# LB_BIT_i31_OSCILLATOR-v03_5_7_-OHW.net
KiCad netlist of a schematic drawn in EAGLE
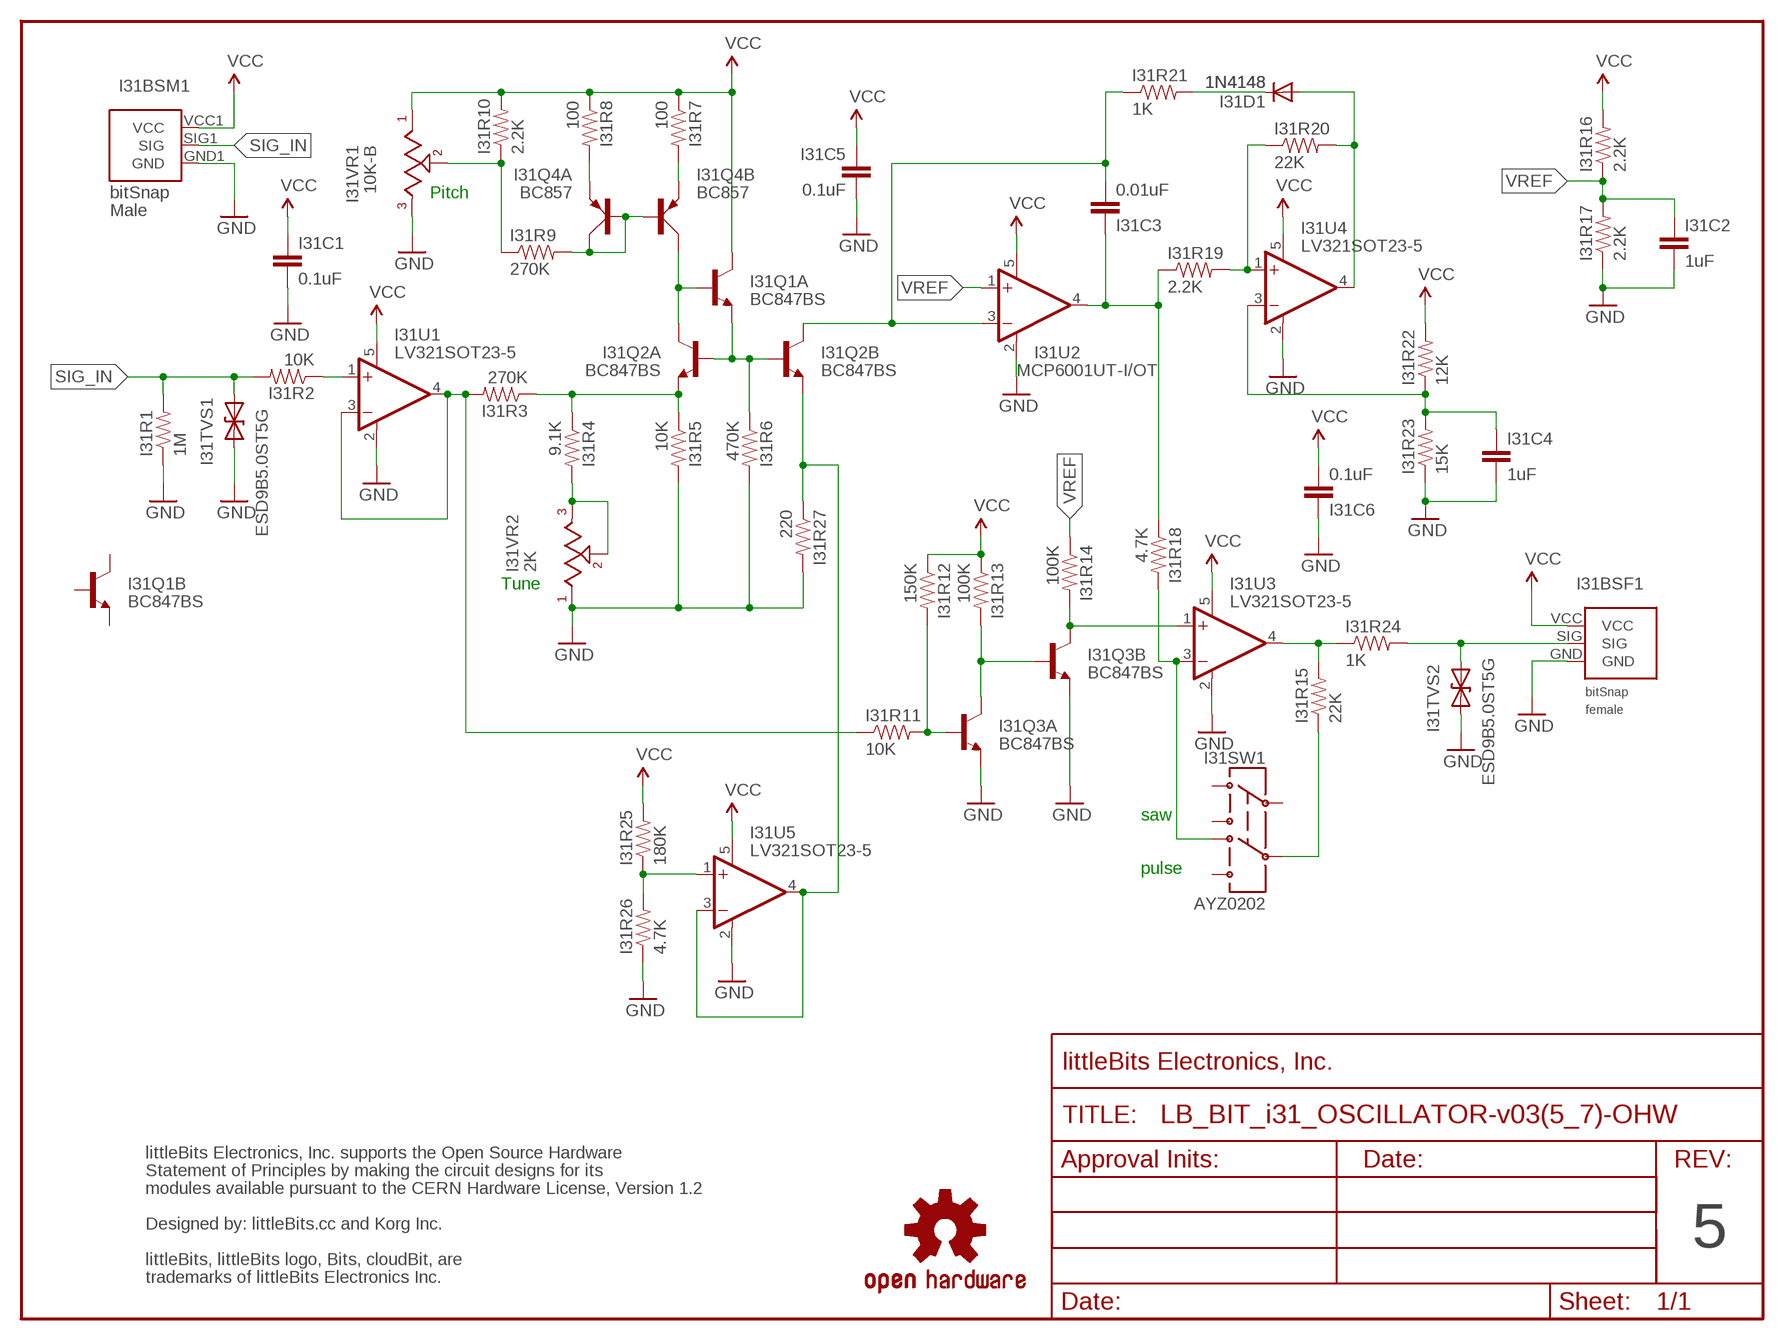
[diagram p0: schematic, sheet 1]

(export (version "E")
  (design (tool "Eeschema 10.0.6"))
  (components
    (comp (ref "I31BSF1")
      (value "BITSNAP_V03_FEMALE")
      (footprint "eagle-import:BITSNAP_V03_FEMALE")
      (libsource (lib "eagle-import") (part "BITSNAP_V03_FEMALE"))
    )
    (comp (ref "I31BSM1")
      (value "BITSNAP_V03_MALE")
      (footprint "eagle-import:BITSNAP_V03_MALE")
      (libsource (lib "eagle-import") (part "BITSNAP_V03_MALE"))
    )
    (comp (ref "I31C1")
      (value "0.1uF")
      (footprint "eagle-import:CAP-0603")
      (libsource (lib "eagle-import") (part "CAPCAP-0603"))
    )
    (comp (ref "I31C2")
      (value "1uF")
      (footprint "eagle-import:CAP-0603")
      (libsource (lib "eagle-import") (part "CAPCAP-0603"))
    )
    (comp (ref "I31C3")
      (value "0.01uF")
      (footprint "eagle-import:CAP-0603")
      (libsource (lib "eagle-import") (part "CAPCAP-0603"))
    )
    (comp (ref "I31C4")
      (value "1uF")
      (footprint "eagle-import:CAP-0603")
      (libsource (lib "eagle-import") (part "CAPCAP-0603"))
    )
    (comp (ref "I31C5")
      (value "0.1uF")
      (footprint "eagle-import:CAP-0603")
      (libsource (lib "eagle-import") (part "CAPCAP-0603"))
    )
    (comp (ref "I31C6")
      (value "0.1uF")
      (footprint "eagle-import:CAP-0603")
      (libsource (lib "eagle-import") (part "CAPCAP-0603"))
    )
    (comp (ref "I31D1")
      (value "1N4148")
      (footprint "eagle-import:SOD-323")
      (libsource (lib "eagle-import") (part "DIODESOD"))
    )
    (comp (ref "I31Q1")
      (value "BC847BS")
      (footprint "eagle-import:SOT-363_PHILLIPS")
      (libsource (lib "eagle-import") (part "TRANS-BJT_NPN-DUAL-BC847BS"))
    )
    (comp (ref "I31Q2")
      (value "BC847BS")
      (footprint "eagle-import:SOT-363_PHILLIPS")
      (libsource (lib "eagle-import") (part "TRANS-BJT_NPN-DUAL-BC847BS"))
    )
    (comp (ref "I31Q3")
      (value "BC847BS")
      (footprint "eagle-import:SOT-363_PHILLIPS")
      (libsource (lib "eagle-import") (part "TRANS-BJT_NPN-DUAL-BC847BS"))
    )
    (comp (ref "I31Q4")
      (value "BC857")
      (footprint "eagle-import:SOT-363_PHILLIPS")
      (libsource (lib "eagle-import") (part "TRANS-BJT_PNP-DUALBC857"))
    )
    (comp (ref "I31R1")
      (value "1M")
      (footprint "eagle-import:RES-0603")
      (libsource (lib "eagle-import") (part "RESISTOR0603"))
    )
    (comp (ref "I31R2")
      (value "10K")
      (footprint "eagle-import:RES-0603")
      (libsource (lib "eagle-import") (part "RESISTOR0603"))
    )
    (comp (ref "I31R3")
      (value "270K")
      (footprint "eagle-import:RES-0603")
      (libsource (lib "eagle-import") (part "RESISTOR0603"))
    )
    (comp (ref "I31R4")
      (value "9.1K")
      (footprint "eagle-import:RES-0603")
      (libsource (lib "eagle-import") (part "RESISTOR0603"))
    )
    (comp (ref "I31R5")
      (value "10K")
      (footprint "eagle-import:RES-0603")
      (libsource (lib "eagle-import") (part "RESISTOR0603"))
    )
    (comp (ref "I31R6")
      (value "470K")
      (footprint "eagle-import:RES-0603")
      (libsource (lib "eagle-import") (part "RESISTOR0603"))
    )
    (comp (ref "I31R7")
      (value "100")
      (footprint "eagle-import:RES-0603")
      (libsource (lib "eagle-import") (part "RESISTOR0603"))
    )
    (comp (ref "I31R8")
      (value "100")
      (footprint "eagle-import:RES-0603")
      (libsource (lib "eagle-import") (part "RESISTOR0603"))
    )
    (comp (ref "I31R9")
      (value "270K")
      (footprint "eagle-import:RES-0603")
      (libsource (lib "eagle-import") (part "RESISTOR0603"))
    )
    (comp (ref "I31R10")
      (value "2.2K")
      (footprint "eagle-import:RES-0603")
      (libsource (lib "eagle-import") (part "RESISTOR0603"))
    )
    (comp (ref "I31R11")
      (value "10K")
      (footprint "eagle-import:RES-0603")
      (libsource (lib "eagle-import") (part "RESISTOR0603"))
    )
    (comp (ref "I31R12")
      (value "150K")
      (footprint "eagle-import:RES-0603")
      (libsource (lib "eagle-import") (part "RESISTOR0603"))
    )
    (comp (ref "I31R13")
      (value "100K")
      (footprint "eagle-import:RES-0603")
      (libsource (lib "eagle-import") (part "RESISTOR0603"))
    )
    (comp (ref "I31R14")
      (value "100K")
      (footprint "eagle-import:RES-0603")
      (libsource (lib "eagle-import") (part "RESISTOR0603"))
    )
    (comp (ref "I31R15")
      (value "22K")
      (footprint "eagle-import:RES-0603")
      (libsource (lib "eagle-import") (part "RESISTOR0603"))
    )
    (comp (ref "I31R16")
      (value "2.2K")
      (footprint "eagle-import:RES-0603")
      (libsource (lib "eagle-import") (part "RESISTOR0603"))
    )
    (comp (ref "I31R17")
      (value "2.2K")
      (footprint "eagle-import:RES-0603")
      (libsource (lib "eagle-import") (part "RESISTOR0603"))
    )
    (comp (ref "I31R18")
      (value "4.7K")
      (footprint "eagle-import:RES-0603")
      (libsource (lib "eagle-import") (part "RESISTOR0603"))
    )
    (comp (ref "I31R19")
      (value "2.2K")
      (footprint "eagle-import:RES-0603")
      (libsource (lib "eagle-import") (part "RESISTOR0603"))
    )
    (comp (ref "I31R20")
      (value "22K")
      (footprint "eagle-import:RES-0603")
      (libsource (lib "eagle-import") (part "RESISTOR0603"))
    )
    (comp (ref "I31R21")
      (value "1K")
      (footprint "eagle-import:RES-0603")
      (libsource (lib "eagle-import") (part "RESISTOR0603"))
    )
    (comp (ref "I31R22")
      (value "12K")
      (footprint "eagle-import:RES-0603")
      (libsource (lib "eagle-import") (part "RESISTOR0603"))
    )
    (comp (ref "I31R23")
      (value "15K")
      (footprint "eagle-import:RES-0603")
      (libsource (lib "eagle-import") (part "RESISTOR0603"))
    )
    (comp (ref "I31R24")
      (value "1K")
      (footprint "eagle-import:RES-0603")
      (libsource (lib "eagle-import") (part "RESISTOR0603"))
    )
    (comp (ref "I31R25")
      (value "180K")
      (footprint "eagle-import:RES-0603")
      (libsource (lib "eagle-import") (part "RESISTOR0603"))
    )
    (comp (ref "I31R26")
      (value "4.7K")
      (footprint "eagle-import:RES-0603")
      (libsource (lib "eagle-import") (part "RESISTOR0603"))
    )
    (comp (ref "I31R27")
      (value "220")
      (footprint "eagle-import:RES-0603")
      (libsource (lib "eagle-import") (part "RESISTOR0603"))
    )
    (comp (ref "I31SW1")
      (value "AYZ0202")
      (footprint "eagle-import:AYZ0202")
      (libsource (lib "eagle-import") (part "AYZ0202"))
    )
    (comp (ref "I31TVS1")
      (value "ESD9B5.0ST5G")
      (footprint "eagle-import:SOD-923")
      (libsource (lib "eagle-import") (part "DIODE-TVSSOD-923"))
    )
    (comp (ref "I31TVS2")
      (value "ESD9B5.0ST5G")
      (footprint "eagle-import:SOD-923")
      (libsource (lib "eagle-import") (part "DIODE-TVSSOD-923"))
    )
    (comp (ref "I31U1")
      (value "LV321SOT23-5")
      (footprint "eagle-import:SOT23-5")
      (libsource (lib "eagle-import") (part "LV321SOT23-5"))
    )
    (comp (ref "I31U2")
      (value "MCP6001UT")
      (footprint "eagle-import:SOT23-5")
      (libsource (lib "eagle-import") (part "LV321SOT23-5"))
    )
    (comp (ref "I31U3")
      (value "LV321SOT23-5")
      (footprint "eagle-import:SOT23-5")
      (libsource (lib "eagle-import") (part "LV321SOT23-5"))
    )
    (comp (ref "I31U4")
      (value "LV321SOT23-5")
      (footprint "eagle-import:SOT23-5")
      (libsource (lib "eagle-import") (part "LV321SOT23-5"))
    )
    (comp (ref "I31U5")
      (value "LV321SOT23-5")
      (footprint "eagle-import:SOT23-5")
      (libsource (lib "eagle-import") (part "LV321SOT23-5"))
    )
    (comp (ref "I31VR1")
      (value "10K-B")
      (footprint "eagle-import:ALPS_POT")
      (libsource (lib "eagle-import") (part "ALPS_POTTH"))
    )
    (comp (ref "I31VR2")
      (value "2K")
      (footprint "eagle-import:THUMBPOT-BOURNS_3352")
      (libsource (lib "eagle-import") (part "THUMBPOT-BOURNS_3352P"))
    )
    (comp (ref "U$2")
      (value "FRAME-LETTER-OHWOHW")
      (footprint "eagle-import:FABDWG01-OHW")
      (libsource (lib "eagle-import") (part "FRAME-LETTER-OHWOHW"))
    )
    (comp (ref "U$3")
      (value "OSHW-LOGOL")
      (footprint "eagle-import:OSHW-LOGO-L")
      (libsource (lib "eagle-import") (part "OSHW-LOGOL"))
    )
    (comp (ref "U$4")
      (value "OSHWCREDIT-KORG")
      (footprint "eagle-import:OSHWCREDIT-KORG")
      (libsource (lib "eagle-import") (part "OSHWCREDIT-KORG"))
    )
  )
  (nets
    (net (code "1") (name "GND") (class "Default")
      (node (ref "I31BSF1") (pin "GND") (pinfunction "GND_GND") (pintype "bidirectional"))
      (node (ref "I31BSM1") (pin "GND1") (pinfunction "GND_GND1") (pintype "bidirectional"))
      (node (ref "I31C1") (pin "2") (pinfunction "2_2") (pintype "passive"))
      (node (ref "I31C2") (pin "2") (pinfunction "2_2") (pintype "passive"))
      (node (ref "I31C4") (pin "2") (pinfunction "2_2") (pintype "passive"))
      (node (ref "I31C5") (pin "2") (pinfunction "2_2") (pintype "passive"))
      (node (ref "I31C6") (pin "1") (pinfunction "1_1") (pintype "passive"))
      (node (ref "I31Q3") (pin "1") (pinfunction "E_1") (pintype "passive"))
      (node (ref "I31Q3") (pin "4") (pinfunction "E_4") (pintype "passive"))
      (node (ref "I31R1") (pin "1") (pinfunction "1_1") (pintype "passive"))
      (node (ref "I31R17") (pin "1") (pinfunction "1_1") (pintype "passive"))
      (node (ref "I31R23") (pin "1") (pinfunction "1_1") (pintype "passive"))
      (node (ref "I31R26") (pin "1") (pinfunction "1_1") (pintype "passive"))
      (node (ref "I31R27") (pin "2") (pinfunction "2_2") (pintype "passive"))
      (node (ref "I31R5") (pin "2") (pinfunction "2_2") (pintype "passive"))
      (node (ref "I31R6") (pin "2") (pinfunction "2_2") (pintype "passive"))
      (node (ref "I31TVS1") (pin "1") (pinfunction "A_1") (pintype "passive"))
      (node (ref "I31TVS2") (pin "1") (pinfunction "A_1") (pintype "passive"))
      (node (ref "I31U1") (pin "2") (pinfunction "V-_2") (pintype "power_in"))
      (node (ref "I31U2") (pin "2") (pinfunction "V-_2") (pintype "power_in"))
      (node (ref "I31U3") (pin "2") (pinfunction "V-_2") (pintype "power_in"))
      (node (ref "I31U4") (pin "2") (pinfunction "V-_2") (pintype "power_in"))
      (node (ref "I31U5") (pin "2") (pinfunction "V-_2") (pintype "power_in"))
      (node (ref "I31VR1") (pin "3") (pinfunction "3_3") (pintype "passive"))
      (node (ref "I31VR2") (pin "3") (pinfunction "1_3") (pintype "passive"))
    )
    (net (code "2") (name "Net-(I31D1-A)") (class "Default")
      (node (ref "I31D1") (pin "2") (pinfunction "A_2") (pintype "passive"))
      (node (ref "I31R20") (pin "2") (pinfunction "2_2") (pintype "passive"))
      (node (ref "I31U4") (pin "4") (pinfunction "OUT_4") (pintype "output"))
    )
    (net (code "3") (name "Net-(I31D1-C)") (class "Default")
      (node (ref "I31D1") (pin "1") (pinfunction "C_1") (pintype "passive"))
      (node (ref "I31R21") (pin "2") (pinfunction "2_2") (pintype "passive"))
    )
    (net (code "4") (name "Net-(I31Q1A-B)") (class "Default")
      (node (ref "I31Q1") (pin "2") (pinfunction "B_2") (pintype "passive"))
      (node (ref "I31Q2") (pin "6") (pinfunction "C_6") (pintype "passive"))
      (node (ref "I31Q4") (pin "3") (pinfunction "C_3") (pintype "passive"))
    )
    (net (code "5") (name "Net-(I31Q1A-E)") (class "Default")
      (node (ref "I31Q1") (pin "1") (pinfunction "E_1") (pintype "passive"))
      (node (ref "I31Q2") (pin "2") (pinfunction "B_2") (pintype "passive"))
      (node (ref "I31Q2") (pin "5") (pinfunction "B_5") (pintype "passive"))
      (node (ref "I31R6") (pin "1") (pinfunction "1_1") (pintype "passive"))
    )
    (net (code "6") (name "Net-(I31Q2A-E)") (class "Default")
      (node (ref "I31Q2") (pin "1") (pinfunction "E_1") (pintype "passive"))
      (node (ref "I31R3") (pin "1") (pinfunction "1_1") (pintype "passive"))
      (node (ref "I31R4") (pin "1") (pinfunction "1_1") (pintype "passive"))
      (node (ref "I31R5") (pin "1") (pinfunction "1_1") (pintype "passive"))
    )
    (net (code "7") (name "Net-(I31Q2B-C)") (class "Default")
      (node (ref "I31C3") (pin "2") (pinfunction "2_2") (pintype "passive"))
      (node (ref "I31Q2") (pin "3") (pinfunction "C_3") (pintype "passive"))
      (node (ref "I31R21") (pin "1") (pinfunction "1_1") (pintype "passive"))
      (node (ref "I31U2") (pin "3") (pinfunction "-IN_3") (pintype "input"))
    )
    (net (code "8") (name "Net-(I31Q2B-E)") (class "Default")
      (node (ref "I31Q2") (pin "4") (pinfunction "E_4") (pintype "passive"))
      (node (ref "I31R27") (pin "1") (pinfunction "1_1") (pintype "passive"))
      (node (ref "I31U5") (pin "3") (pinfunction "-IN_3") (pintype "input"))
      (node (ref "I31U5") (pin "4") (pinfunction "OUT_4") (pintype "output"))
    )
    (net (code "9") (name "Net-(I31Q3A-B)") (class "Default")
      (node (ref "I31Q3") (pin "2") (pinfunction "B_2") (pintype "passive"))
      (node (ref "I31R11") (pin "2") (pinfunction "2_2") (pintype "passive"))
      (node (ref "I31R12") (pin "2") (pinfunction "2_2") (pintype "passive"))
    )
    (net (code "10") (name "Net-(I31Q3A-C)") (class "Default")
      (node (ref "I31Q3") (pin "5") (pinfunction "B_5") (pintype "passive"))
      (node (ref "I31Q3") (pin "6") (pinfunction "C_6") (pintype "passive"))
      (node (ref "I31R13") (pin "2") (pinfunction "2_2") (pintype "passive"))
    )
    (net (code "11") (name "Net-(I31Q3B-C)") (class "Default")
      (node (ref "I31Q3") (pin "3") (pinfunction "C_3") (pintype "passive"))
      (node (ref "I31R14") (pin "2") (pinfunction "2_2") (pintype "passive"))
      (node (ref "I31U3") (pin "1") (pinfunction "+IN_1") (pintype "input"))
    )
    (net (code "12") (name "Net-(I31Q4A-B)") (class "Default")
      (node (ref "I31Q4") (pin "2") (pinfunction "B_2") (pintype "passive"))
      (node (ref "I31Q4") (pin "5") (pinfunction "B_5") (pintype "passive"))
      (node (ref "I31Q4") (pin "6") (pinfunction "C_6") (pintype "passive"))
      (node (ref "I31R9") (pin "2") (pinfunction "2_2") (pintype "passive"))
    )
    (net (code "13") (name "Net-(I31Q4A-E)") (class "Default")
      (node (ref "I31Q4") (pin "1") (pinfunction "E_1") (pintype "passive"))
      (node (ref "I31R8") (pin "2") (pinfunction "2_2") (pintype "passive"))
    )
    (net (code "14") (name "Net-(I31Q4B-E)") (class "Default")
      (node (ref "I31Q4") (pin "4") (pinfunction "E_4") (pintype "passive"))
      (node (ref "I31R7") (pin "2") (pinfunction "2_2") (pintype "passive"))
    )
    (net (code "15") (name "Net-(I31R10-Pad1)") (class "Default")
      (node (ref "I31R10") (pin "1") (pinfunction "1_1") (pintype "passive"))
      (node (ref "I31R9") (pin "1") (pinfunction "1_1") (pintype "passive"))
      (node (ref "I31VR1") (pin "2") (pinfunction "2_2") (pintype "passive"))
    )
    (net (code "16") (name "Net-(I31R15-Pad1)") (class "Default")
      (node (ref "I31R15") (pin "1") (pinfunction "1_1") (pintype "passive"))
      (node (ref "I31SW1") (pin "5") (pinfunction "5_5") (pintype "bidirectional"))
    )
    (net (code "17") (name "Net-(I31TVS2-C)") (class "Default")
      (node (ref "I31BSF1") (pin "SIG") (pinfunction "SIG_SIG") (pintype "bidirectional"))
      (node (ref "I31R24") (pin "2") (pinfunction "2_2") (pintype "passive"))
      (node (ref "I31TVS2") (pin "2") (pinfunction "C_2") (pintype "passive"))
    )
    (net (code "18") (name "Net-(I31U1-+IN)") (class "Default")
      (node (ref "I31R2") (pin "1") (pinfunction "1_1") (pintype "passive"))
      (node (ref "I31U1") (pin "1") (pinfunction "+IN_1") (pintype "input"))
    )
    (net (code "19") (name "Net-(I31U1--IN)") (class "Default")
      (node (ref "I31R11") (pin "1") (pinfunction "1_1") (pintype "passive"))
      (node (ref "I31R3") (pin "2") (pinfunction "2_2") (pintype "passive"))
      (node (ref "I31U1") (pin "3") (pinfunction "-IN_3") (pintype "input"))
      (node (ref "I31U1") (pin "4") (pinfunction "OUT_4") (pintype "output"))
    )
    (net (code "20") (name "Net-(I31U2-OUT)") (class "Default")
      (node (ref "I31C3") (pin "1") (pinfunction "1_1") (pintype "passive"))
      (node (ref "I31R18") (pin "1") (pinfunction "1_1") (pintype "passive"))
      (node (ref "I31R19") (pin "1") (pinfunction "1_1") (pintype "passive"))
      (node (ref "I31U2") (pin "4") (pinfunction "OUT_4") (pintype "output"))
    )
    (net (code "21") (name "Net-(I31U3--IN)") (class "Default")
      (node (ref "I31R18") (pin "2") (pinfunction "2_2") (pintype "passive"))
      (node (ref "I31SW1") (pin "4") (pinfunction "4_4") (pintype "bidirectional"))
      (node (ref "I31U3") (pin "3") (pinfunction "-IN_3") (pintype "input"))
    )
    (net (code "22") (name "Net-(I31U3-OUT)") (class "Default")
      (node (ref "I31R15") (pin "2") (pinfunction "2_2") (pintype "passive"))
      (node (ref "I31R24") (pin "1") (pinfunction "1_1") (pintype "passive"))
      (node (ref "I31U3") (pin "4") (pinfunction "OUT_4") (pintype "output"))
    )
    (net (code "23") (name "Net-(I31U4-+IN)") (class "Default")
      (node (ref "I31R19") (pin "2") (pinfunction "2_2") (pintype "passive"))
      (node (ref "I31R20") (pin "1") (pinfunction "1_1") (pintype "passive"))
      (node (ref "I31U4") (pin "1") (pinfunction "+IN_1") (pintype "input"))
    )
    (net (code "24") (name "Net-(I31U4--IN)") (class "Default")
      (node (ref "I31C4") (pin "1") (pinfunction "1_1") (pintype "passive"))
      (node (ref "I31R22") (pin "1") (pinfunction "1_1") (pintype "passive"))
      (node (ref "I31R23") (pin "2") (pinfunction "2_2") (pintype "passive"))
      (node (ref "I31U4") (pin "3") (pinfunction "-IN_3") (pintype "input"))
    )
    (net (code "25") (name "Net-(I31U5-+IN)") (class "Default")
      (node (ref "I31R25") (pin "1") (pinfunction "1_1") (pintype "passive"))
      (node (ref "I31R26") (pin "2") (pinfunction "2_2") (pintype "passive"))
      (node (ref "I31U5") (pin "1") (pinfunction "+IN_1") (pintype "input"))
    )
    (net (code "26") (name "Net-(I31VR2-3)") (class "Default")
      (node (ref "I31R4") (pin "2") (pinfunction "2_2") (pintype "passive"))
      (node (ref "I31VR2") (pin "1") (pinfunction "3_1") (pintype "passive"))
      (node (ref "I31VR2") (pin "2") (pinfunction "2_2") (pintype "passive"))
    )
    (net (code "27") (name "SIG_IN") (class "Default")
      (node (ref "I31BSM1") (pin "SIG1") (pinfunction "SIG_SIG1") (pintype "bidirectional"))
      (node (ref "I31R1") (pin "2") (pinfunction "2_2") (pintype "passive"))
      (node (ref "I31R2") (pin "2") (pinfunction "2_2") (pintype "passive"))
      (node (ref "I31TVS1") (pin "2") (pinfunction "C_2") (pintype "passive"))
    )
    (net (code "28") (name "VCC") (class "Default")
      (node (ref "I31BSF1") (pin "VCC") (pinfunction "VCC_VCC") (pintype "bidirectional"))
      (node (ref "I31BSM1") (pin "VCC1") (pinfunction "VCC_VCC1") (pintype "bidirectional"))
      (node (ref "I31C1") (pin "1") (pinfunction "1_1") (pintype "passive"))
      (node (ref "I31C5") (pin "1") (pinfunction "1_1") (pintype "passive"))
      (node (ref "I31C6") (pin "2") (pinfunction "2_2") (pintype "passive"))
      (node (ref "I31Q1") (pin "6") (pinfunction "C_6") (pintype "passive"))
      (node (ref "I31R10") (pin "2") (pinfunction "2_2") (pintype "passive"))
      (node (ref "I31R12") (pin "1") (pinfunction "1_1") (pintype "passive"))
      (node (ref "I31R13") (pin "1") (pinfunction "1_1") (pintype "passive"))
      (node (ref "I31R16") (pin "2") (pinfunction "2_2") (pintype "passive"))
      (node (ref "I31R22") (pin "2") (pinfunction "2_2") (pintype "passive"))
      (node (ref "I31R25") (pin "2") (pinfunction "2_2") (pintype "passive"))
      (node (ref "I31R7") (pin "1") (pinfunction "1_1") (pintype "passive"))
      (node (ref "I31R8") (pin "1") (pinfunction "1_1") (pintype "passive"))
      (node (ref "I31U1") (pin "5") (pinfunction "V+_5") (pintype "power_in"))
      (node (ref "I31U2") (pin "5") (pinfunction "V+_5") (pintype "power_in"))
      (node (ref "I31U3") (pin "5") (pinfunction "V+_5") (pintype "power_in"))
      (node (ref "I31U4") (pin "5") (pinfunction "V+_5") (pintype "power_in"))
      (node (ref "I31U5") (pin "5") (pinfunction "V+_5") (pintype "power_in"))
      (node (ref "I31VR1") (pin "1") (pinfunction "1_1") (pintype "passive"))
    )
    (net (code "29") (name "VREF") (class "Default")
      (node (ref "I31C2") (pin "1") (pinfunction "1_1") (pintype "passive"))
      (node (ref "I31R14") (pin "1") (pinfunction "1_1") (pintype "passive"))
      (node (ref "I31R16") (pin "1") (pinfunction "1_1") (pintype "passive"))
      (node (ref "I31R17") (pin "2") (pinfunction "2_2") (pintype "passive"))
      (node (ref "I31U2") (pin "1") (pinfunction "+IN_1") (pintype "input"))
    )
    (net (code "30") (name "unconnected-(I31Q1B-B-Pad5)") (class "Default")
      (node (ref "I31Q1") (pin "5") (pinfunction "B_5") (pintype "passive"))
    )
    (net (code "31") (name "unconnected-(I31Q1B-C-Pad3)") (class "Default")
      (node (ref "I31Q1") (pin "3") (pinfunction "C_3") (pintype "passive"))
    )
    (net (code "32") (name "unconnected-(I31Q1B-E-Pad4)") (class "Default")
      (node (ref "I31Q1") (pin "4") (pinfunction "E_4") (pintype "passive"))
    )
    (net (code "33") (name "unconnected-(I31SW1-Pad1)") (class "Default")
      (node (ref "I31SW1") (pin "1") (pinfunction "1_1") (pintype "bidirectional"))
    )
    (net (code "34") (name "unconnected-(I31SW1-Pad2)") (class "Default")
      (node (ref "I31SW1") (pin "2") (pinfunction "2_2") (pintype "bidirectional"))
    )
    (net (code "35") (name "unconnected-(I31SW1-Pad3)") (class "Default")
      (node (ref "I31SW1") (pin "3") (pinfunction "3_3") (pintype "bidirectional"))
    )
    (net (code "36") (name "unconnected-(I31SW1-Pad6)") (class "Default")
      (node (ref "I31SW1") (pin "6") (pinfunction "6_6") (pintype "bidirectional"))
    )
  )
)
